# Analogue.net
KiCad netlist of a schematic drawn in Altium Designer
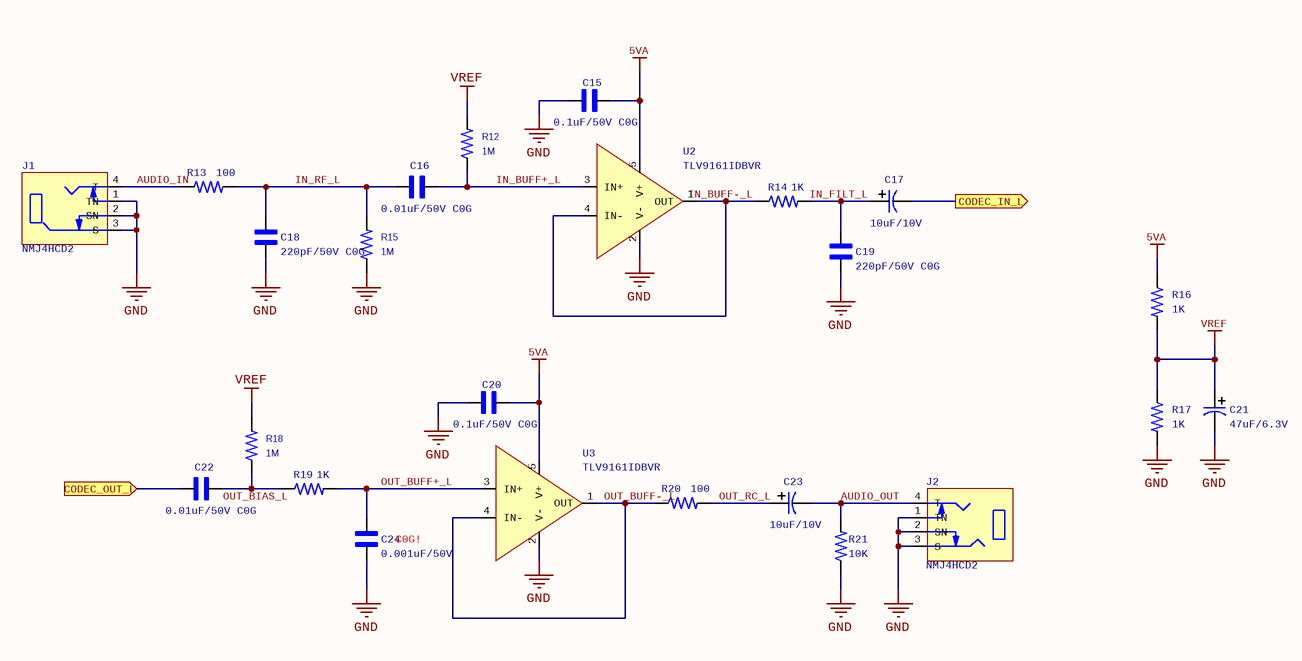
[diagram p0: Analogue.SchDoc]

(export (version "E")
  (design (tool "Eeschema 10.0.6"))
  (components
    (comp (ref "C15")
      (value "0.1uF/50V C0G")
      (footprint "C0603")
      (description "MLCC 0.1uF 50V C0G 10% 0603")
      (fields
        (field (name "MANUFACTURER") "TDK")
        (field (name "MANUFACTURER PART NUMBER") "C1608X5R1H104K080AA")
      )
      (libsource (lib "Capacitors") (part "C0603 0.1uF/50V"))
    )
    (comp (ref "C16")
      (value "0.01uF/50V C0G")
      (footprint "C0603")
      (description "MLCC 0.01uF 50V C0G 5% 0603")
      (fields
        (field (name "MANUFACTURER") "Murata")
        (field (name "MANUFACTURER PART NUMBER") "GRM1885C1H103JA01J")
      )
      (libsource (lib "Capacitors") (part "C0603 0.01uF/50V C0G"))
    )
    (comp (ref "C17")
      (value "10uF/10V")
      (footprint "EIA1206")
      (description "Tantalum Capacitors - Solid SMD 10V 10uF 10%")
      (fields
        (field (name "MANUFACTURER") "KEMET")
        (field (name "MANUFACTURER PART NUMBER") "T491A106K010AT")
      )
      (libsource (lib "Capacitors") (part "TANT 10UF/10V"))
    )
    (comp (ref "C18")
      (value "220pF/50V C0G")
      (footprint "C0603")
      (description "MLCC 220pF 50V C0G 5% 0603")
      (fields
        (field (name "MANUFACTURER") "KEMET")
        (field (name "MANUFACTURER PART NUMBER") "C0603C221J5GACTU")
      )
      (libsource (lib "Capacitors") (part "C0603 220pF/50V C0G"))
    )
    (comp (ref "C19")
      (value "220pF/50V C0G")
      (footprint "C0603")
      (description "MLCC 220pF 50V C0G 5% 0603")
      (fields
        (field (name "MANUFACTURER") "KEMET")
        (field (name "MANUFACTURER PART NUMBER") "C0603C221J5GACTU")
      )
      (libsource (lib "Capacitors") (part "C0603 220pF/50V C0G"))
    )
    (comp (ref "C20")
      (value "0.1uF/50V C0G")
      (footprint "C0603")
      (description "MLCC 0.1uF 50V C0G 10% 0603")
      (fields
        (field (name "MANUFACTURER") "TDK")
        (field (name "MANUFACTURER PART NUMBER") "C1608X5R1H104K080AA")
      )
      (libsource (lib "Capacitors") (part "C0603 0.1uF/50V"))
    )
    (comp (ref "C21")
      (value "47uF/6.3V")
      (footprint "EIA1206")
      (description "Tantalum Capacitors - Solid SMD 6.3V 47uF 10%")
      (fields
        (field (name "MANUFACTURER") "Kyocera AVX")
        (field (name "MANUFACTURER PART NUMBER") "TAJA476K006SNJV")
      )
      (libsource (lib "Capacitors") (part "TANT 47UF/6.3V"))
    )
    (comp (ref "C22")
      (value "0.01uF/50V C0G")
      (footprint "C0603")
      (description "MLCC 0.01uF 50V C0G 5% 0603")
      (fields
        (field (name "MANUFACTURER") "Murata")
        (field (name "MANUFACTURER PART NUMBER") "GRM1885C1H103JA01J")
      )
      (libsource (lib "Capacitors") (part "C0603 0.01uF/50V C0G"))
    )
    (comp (ref "C23")
      (value "10uF/10V")
      (footprint "EIA1206")
      (description "Tantalum Capacitors - Solid SMD 10V 10uF 10%")
      (fields
        (field (name "MANUFACTURER") "KEMET")
        (field (name "MANUFACTURER PART NUMBER") "T491A106K010AT")
      )
      (libsource (lib "Capacitors") (part "TANT 10UF/10V"))
    )
    (comp (ref "C24")
      (value "0.001uF/50V")
      (footprint "C0603")
      (description "MLCC 0.001uF 50V X5R 10% 0603")
      (fields
        (field (name "MANUFACTURER") "Samsung")
        (field (name "MANUFACTURER PART NUMBER") "CL10B102KB8NNNL")
      )
      (libsource (lib "Capacitors") (part "C0603 0.001uF/50V"))
    )
    (comp (ref "J1")
      (value "NMJ4HCD2")
      (footprint "NMJ4HCD2")
      (description "Phone Connectors 2C MONO 2-SPST NC")
      (fields (field (name "MANUFACTURER") "Neutrik"))
      (libsource (lib "") (part "TS Audio Jack 6.3mm_1"))
    )
    (comp (ref "J2")
      (value "NMJ4HCD2")
      (footprint "NMJ4HCD2")
      (description "Phone Connectors 2C MONO 2-SPST NC")
      (fields (field (name "MANUFACTURER") "Neutrik"))
      (libsource (lib "Connectors") (part "TS Audio Jack 6.3mm"))
    )
    (comp (ref "R12")
      (value "1M")
      (footprint "R0603")
      (description "RES SMD 1M OHM 1% 1/10W 0603")
      (fields
        (field (name "MANUFACTURER") "Yageo")
        (field (name "MANUFACTURER PART NUMBER") "RC0603FR-071ML")
      )
      (libsource (lib "Resistors") (part "R0603 1M"))
    )
    (comp (ref "R13")
      (value "100")
      (footprint "R0603")
      (description "RES 0603 100 OHM 1% 1/10W")
      (fields
        (field (name "MANUFACTURER") "Yageo")
        (field (name "MANUFACTURER PART NUMBER") "RC0603FR-07100RL")
      )
      (libsource (lib "Resistors") (part "R0603 100"))
    )
    (comp (ref "R14")
      (value "1K")
      (footprint "R0603")
      (description "Res Thick Film 0603 1K Ohm 1% 1/10W ±50ppm/°C Molded SMD Paper T/R")
      (fields
        (field (name "MANUFACTURER") "Yageo")
        (field (name "MANUFACTURER PART NUMBER") "RE0603FRE071KL")
      )
      (libsource (lib "Resistors") (part "R0603 1K"))
    )
    (comp (ref "R15")
      (value "1M")
      (footprint "R0603")
      (description "RES SMD 1M OHM 1% 1/10W 0603")
      (fields
        (field (name "MANUFACTURER") "Yageo")
        (field (name "MANUFACTURER PART NUMBER") "RC0603FR-071ML")
      )
      (libsource (lib "Resistors") (part "R0603 1M"))
    )
    (comp (ref "R16")
      (value "1K")
      (footprint "R0603")
      (description "Res Thick Film 0603 1K Ohm 1% 1/10W ±50ppm/°C Molded SMD Paper T/R")
      (fields
        (field (name "MANUFACTURER") "Yageo")
        (field (name "MANUFACTURER PART NUMBER") "RE0603FRE071KL")
      )
      (libsource (lib "Resistors") (part "R0603 1K"))
    )
    (comp (ref "R17")
      (value "1K")
      (footprint "R0603")
      (description "Res Thick Film 0603 1K Ohm 1% 1/10W ±50ppm/°C Molded SMD Paper T/R")
      (fields
        (field (name "MANUFACTURER") "Yageo")
        (field (name "MANUFACTURER PART NUMBER") "RE0603FRE071KL")
      )
      (libsource (lib "Resistors") (part "R0603 1K"))
    )
    (comp (ref "R18")
      (value "1M")
      (footprint "R0603")
      (description "RES SMD 1M OHM 1% 1/10W 0603")
      (fields
        (field (name "MANUFACTURER") "Yageo")
        (field (name "MANUFACTURER PART NUMBER") "RC0603FR-071ML")
      )
      (libsource (lib "Resistors") (part "R0603 1M"))
    )
    (comp (ref "R19")
      (value "1K")
      (footprint "R0603")
      (description "Res Thick Film 0603 1K Ohm 1% 1/10W ±50ppm/°C Molded SMD Paper T/R")
      (fields
        (field (name "MANUFACTURER") "Yageo")
        (field (name "MANUFACTURER PART NUMBER") "RE0603FRE071KL")
      )
      (libsource (lib "Resistors") (part "R0603 1K"))
    )
    (comp (ref "R20")
      (value "100")
      (footprint "R0603")
      (description "RES 0603 100 OHM 1% 1/10W")
      (fields
        (field (name "MANUFACTURER") "Yageo")
        (field (name "MANUFACTURER PART NUMBER") "RC0603FR-07100RL")
      )
      (libsource (lib "Resistors") (part "R0603 100"))
    )
    (comp (ref "R21")
      (value "10K")
      (footprint "R0603")
      (description "RES 0603 10K OHM 1% 1/10W")
      (fields
        (field (name "MANUFACTURER") "Yageo")
        (field (name "MANUFACTURER PART NUMBER") "RC0603FR-0710KP")
      )
      (libsource (lib "Resistors") (part "R0603 10K"))
    )
    (comp (ref "U2")
      (value "TLV9161IDBVR")
      (footprint "SOT23-5")
      (fields (field (name "MANUFACTURER") "Texas Instruments"))
      (libsource (lib "IC Amplifier") (part "TLV9161IDBVR"))
    )
    (comp (ref "U3")
      (value "TLV9161IDBVR")
      (footprint "SOT23-5")
      (fields (field (name "MANUFACTURER") "Texas Instruments"))
      (libsource (lib "IC Amplifier") (part "TLV9161IDBVR"))
    )
  )
  (nets
    (net (code "1") (name "/AUDIO_IN") (class "Default")
      (node (ref "J1") (pin "4") (pinfunction "T_4") (pintype "passive"))
      (node (ref "R13") (pin "1") (pinfunction "1_1") (pintype "passive"))
    )
    (net (code "2") (name "/AUDIO_OUT") (class "Default")
      (node (ref "C23") (pin "2") (pinfunction "2_2") (pintype "passive"))
      (node (ref "J2") (pin "4") (pinfunction "T_4") (pintype "passive"))
      (node (ref "R21") (pin "2") (pinfunction "2_2") (pintype "passive"))
    )
    (net (code "3") (name "/CODEC_IN_L") (class "Default")
      (node (ref "C17") (pin "2") (pinfunction "2_2") (pintype "passive"))
    )
    (net (code "4") (name "/CODEC_OUT_L") (class "Default")
      (node (ref "C22") (pin "1") (pinfunction "1_1") (pintype "passive"))
    )
    (net (code "5") (name "/IN_BUFF+_L") (class "Default")
      (node (ref "C16") (pin "2") (pinfunction "2_2") (pintype "passive"))
      (node (ref "R12") (pin "1") (pinfunction "1_1") (pintype "passive"))
      (node (ref "U2") (pin "3") (pinfunction "IN+_3") (pintype "passive"))
    )
    (net (code "6") (name "/IN_BUFF-_L") (class "Default")
      (node (ref "R14") (pin "1") (pinfunction "1_1") (pintype "passive"))
      (node (ref "U2") (pin "1") (pinfunction "OUT_1") (pintype "passive"))
      (node (ref "U2") (pin "4") (pinfunction "IN-_4") (pintype "passive"))
    )
    (net (code "7") (name "/IN_FILT_L") (class "Default")
      (node (ref "C17") (pin "1") (pinfunction "1_1") (pintype "passive"))
      (node (ref "C19") (pin "1") (pinfunction "1_1") (pintype "passive"))
      (node (ref "R14") (pin "2") (pinfunction "2_2") (pintype "passive"))
    )
    (net (code "8") (name "/IN_RF_L") (class "Default")
      (node (ref "C16") (pin "1") (pinfunction "1_1") (pintype "passive"))
      (node (ref "C18") (pin "1") (pinfunction "1_1") (pintype "passive"))
      (node (ref "R13") (pin "2") (pinfunction "2_2") (pintype "passive"))
      (node (ref "R15") (pin "2") (pinfunction "2_2") (pintype "passive"))
    )
    (net (code "9") (name "/OUT_BIAS_L") (class "Default")
      (node (ref "C22") (pin "2") (pinfunction "2_2") (pintype "passive"))
      (node (ref "R18") (pin "1") (pinfunction "1_1") (pintype "passive"))
      (node (ref "R19") (pin "1") (pinfunction "1_1") (pintype "passive"))
    )
    (net (code "10") (name "/OUT_BUFF+_L") (class "Default")
      (node (ref "C24") (pin "2") (pinfunction "2_2") (pintype "passive"))
      (node (ref "R19") (pin "2") (pinfunction "2_2") (pintype "passive"))
      (node (ref "U3") (pin "3") (pinfunction "IN+_3") (pintype "passive"))
    )
    (net (code "11") (name "/OUT_BUFF-_L") (class "Default")
      (node (ref "R20") (pin "1") (pinfunction "1_1") (pintype "passive"))
      (node (ref "U3") (pin "1") (pinfunction "OUT_1") (pintype "passive"))
      (node (ref "U3") (pin "4") (pinfunction "IN-_4") (pintype "passive"))
    )
    (net (code "12") (name "/OUT_RC_L") (class "Default")
      (node (ref "C23") (pin "1") (pinfunction "1_1") (pintype "passive"))
      (node (ref "R20") (pin "2") (pinfunction "2_2") (pintype "passive"))
    )
    (net (code "13") (name "5VA") (class "Default")
      (node (ref "C15") (pin "1") (pinfunction "1_1") (pintype "passive"))
      (node (ref "C20") (pin "1") (pinfunction "1_1") (pintype "passive"))
      (node (ref "R16") (pin "1") (pinfunction "1_1") (pintype "passive"))
      (node (ref "U2") (pin "5") (pinfunction "V+_5") (pintype "passive"))
      (node (ref "U3") (pin "5") (pinfunction "V+_5") (pintype "passive"))
    )
    (net (code "14") (name "GND") (class "Default")
      (node (ref "C15") (pin "2") (pinfunction "2_2") (pintype "passive"))
      (node (ref "C18") (pin "2") (pinfunction "2_2") (pintype "passive"))
      (node (ref "C19") (pin "2") (pinfunction "2_2") (pintype "passive"))
      (node (ref "C20") (pin "2") (pinfunction "2_2") (pintype "passive"))
      (node (ref "C21") (pin "2") (pinfunction "2_2") (pintype "passive"))
      (node (ref "C24") (pin "1") (pinfunction "1_1") (pintype "passive"))
      (node (ref "J1") (pin "1") (pinfunction "TN_1") (pintype "passive"))
      (node (ref "J1") (pin "2") (pinfunction "SN_2") (pintype "passive"))
      (node (ref "J1") (pin "3") (pinfunction "S_3") (pintype "passive"))
      (node (ref "J2") (pin "1") (pinfunction "TN_1") (pintype "passive"))
      (node (ref "J2") (pin "2") (pinfunction "SN_2") (pintype "passive"))
      (node (ref "J2") (pin "3") (pinfunction "S_3") (pintype "passive"))
      (node (ref "R15") (pin "1") (pinfunction "1_1") (pintype "passive"))
      (node (ref "R17") (pin "2") (pinfunction "2_2") (pintype "passive"))
      (node (ref "R21") (pin "1") (pinfunction "1_1") (pintype "passive"))
      (node (ref "U2") (pin "2") (pinfunction "V-_2") (pintype "passive"))
      (node (ref "U3") (pin "2") (pinfunction "V-_2") (pintype "passive"))
    )
    (net (code "15") (name "VREF") (class "Default")
      (node (ref "C21") (pin "1") (pinfunction "1_1") (pintype "passive"))
      (node (ref "R12") (pin "2") (pinfunction "2_2") (pintype "passive"))
      (node (ref "R16") (pin "2") (pinfunction "2_2") (pintype "passive"))
      (node (ref "R17") (pin "1") (pinfunction "1_1") (pintype "passive"))
      (node (ref "R18") (pin "2") (pinfunction "2_2") (pintype "passive"))
    )
  )
)
